# v1_1_0.net
KiCad netlist of a schematic drawn in EAGLE
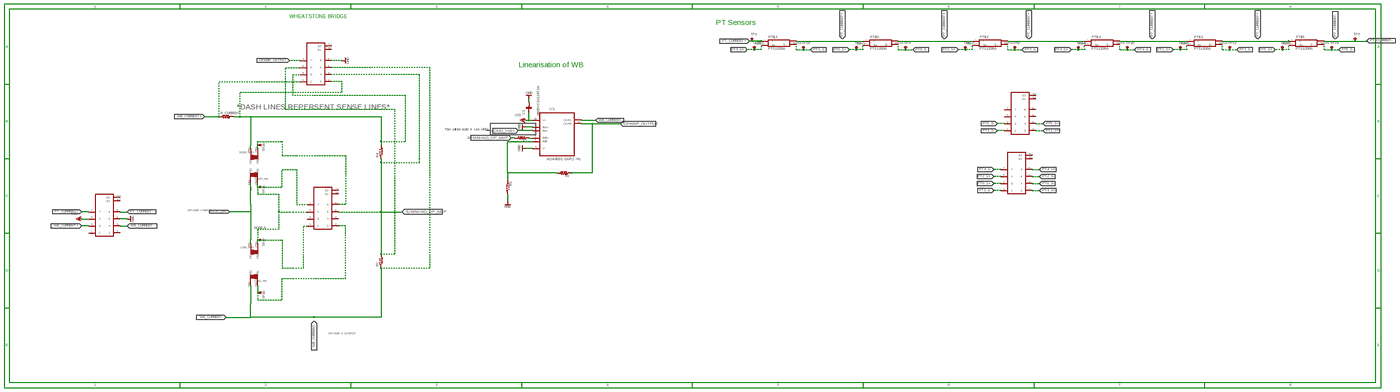
[diagram p0: schematic, sheet 1, overview]
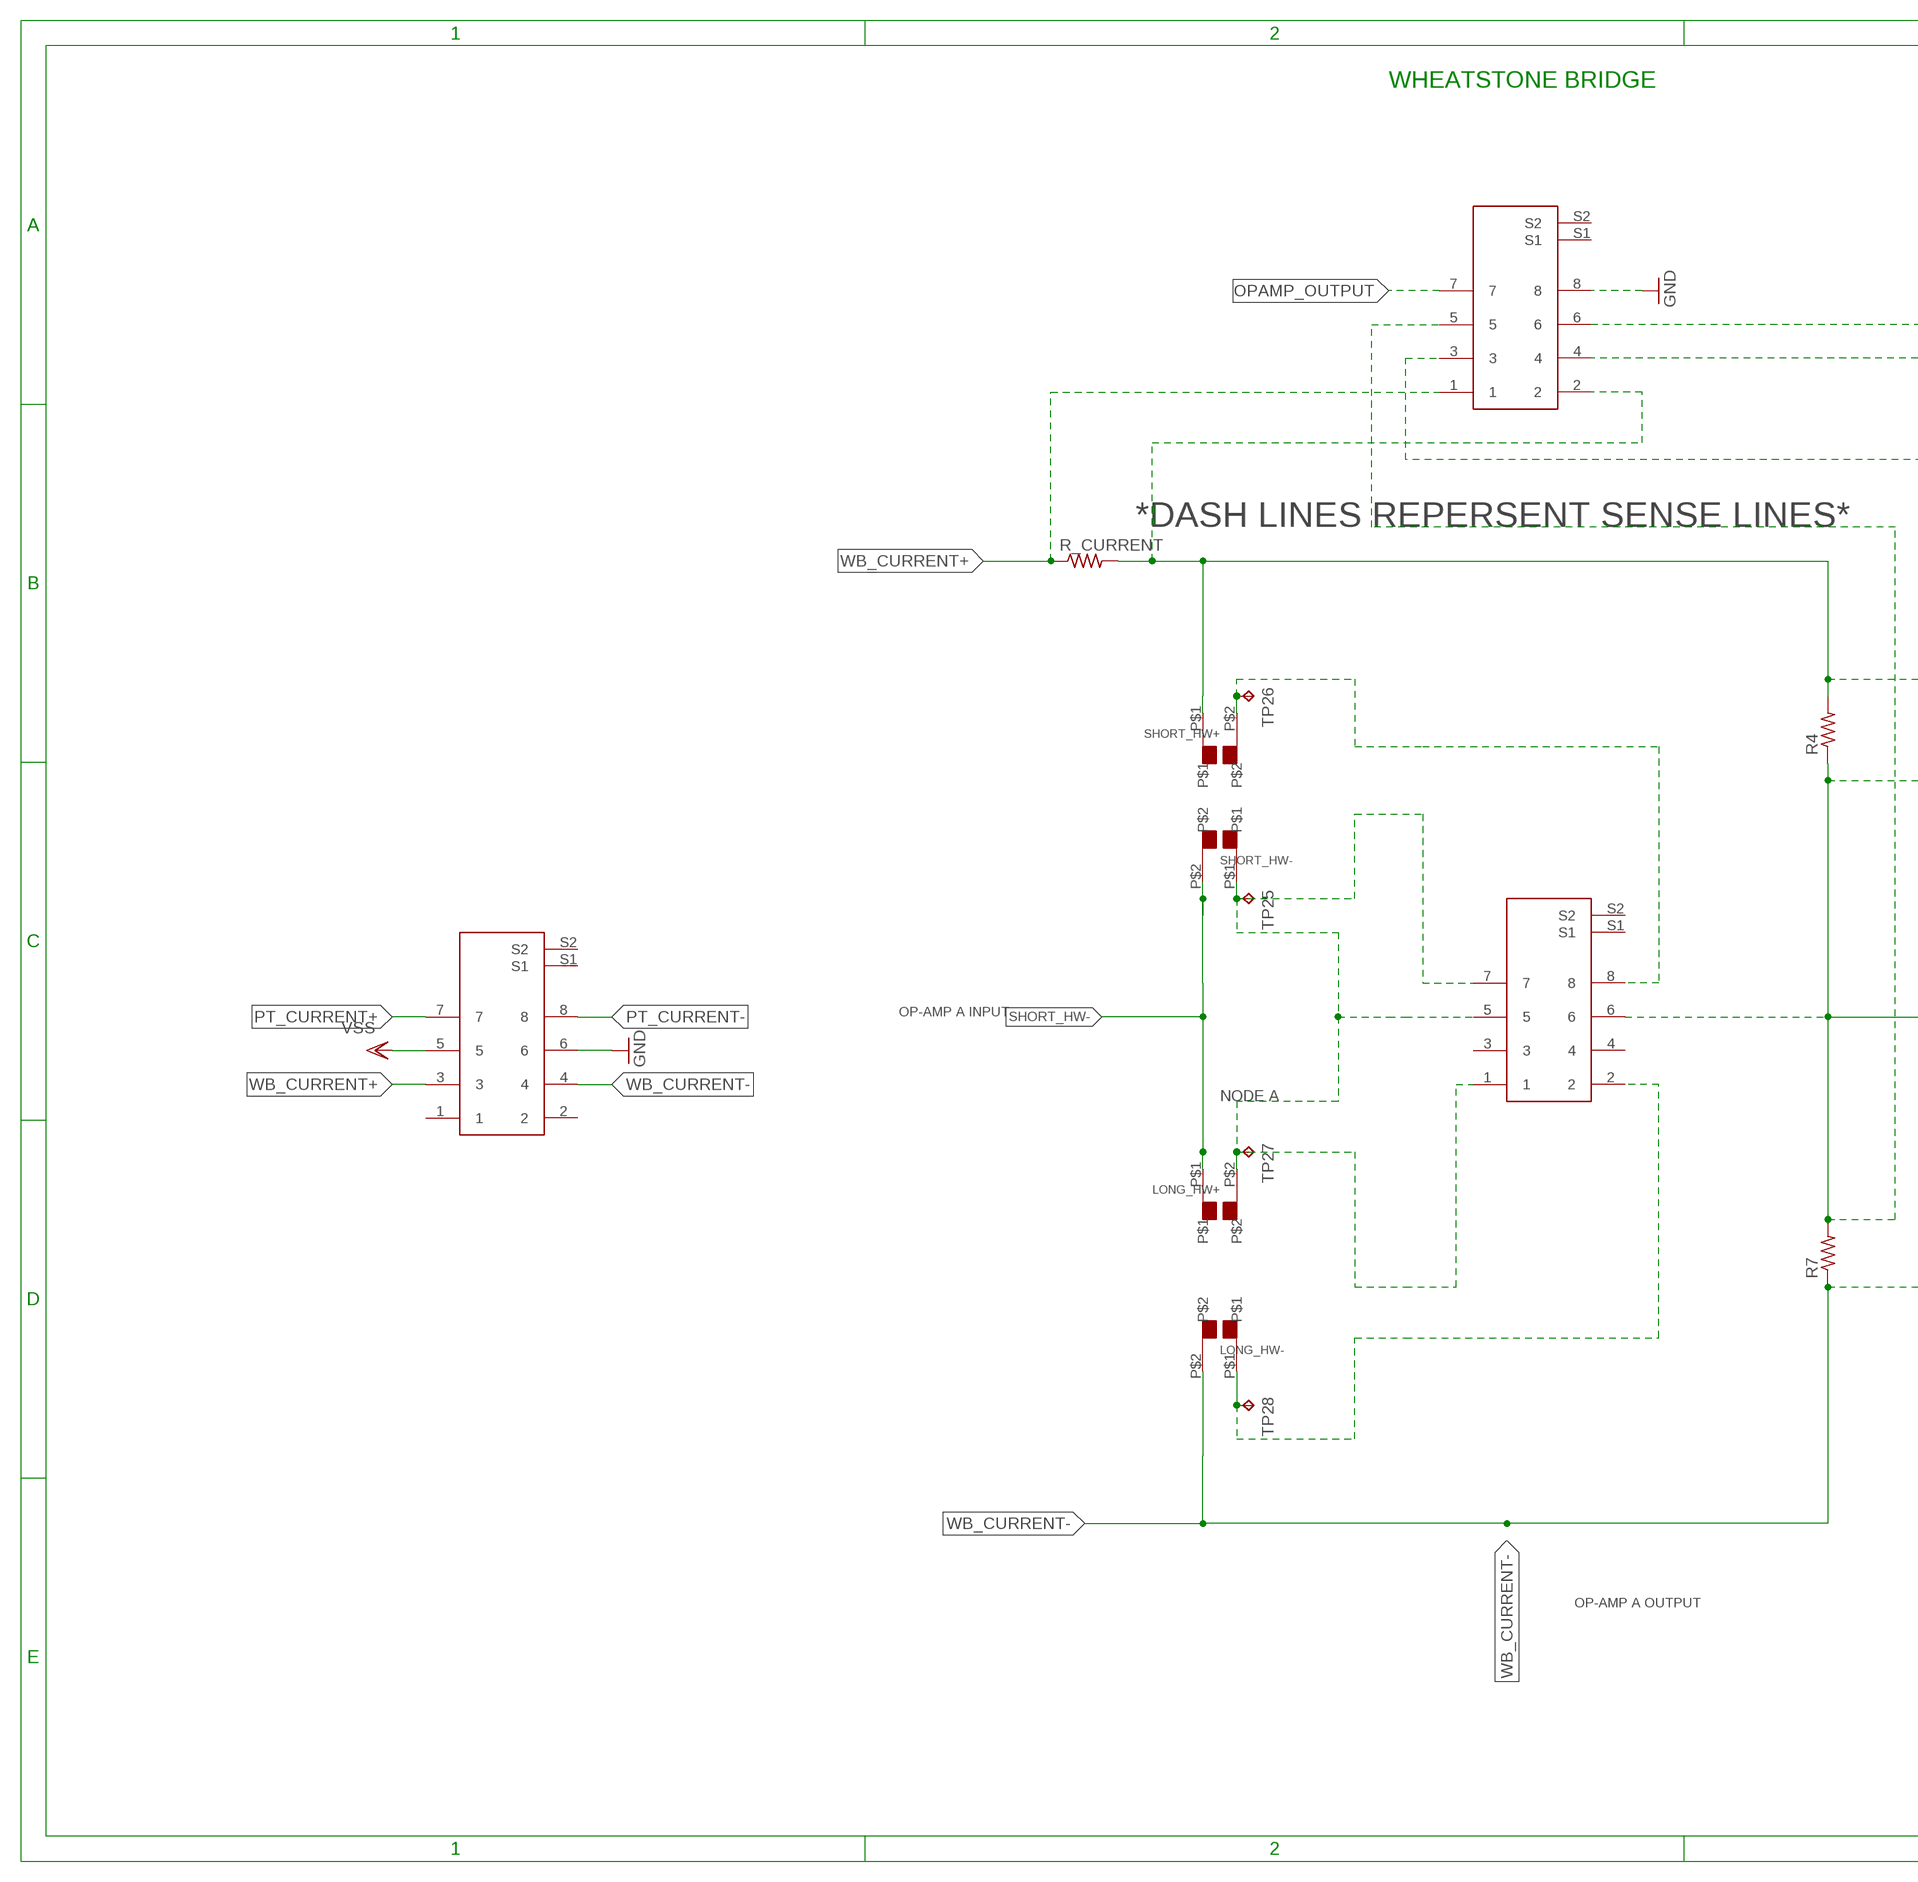
[diagram p1: schematic, sheet 1, part 1 of 4]
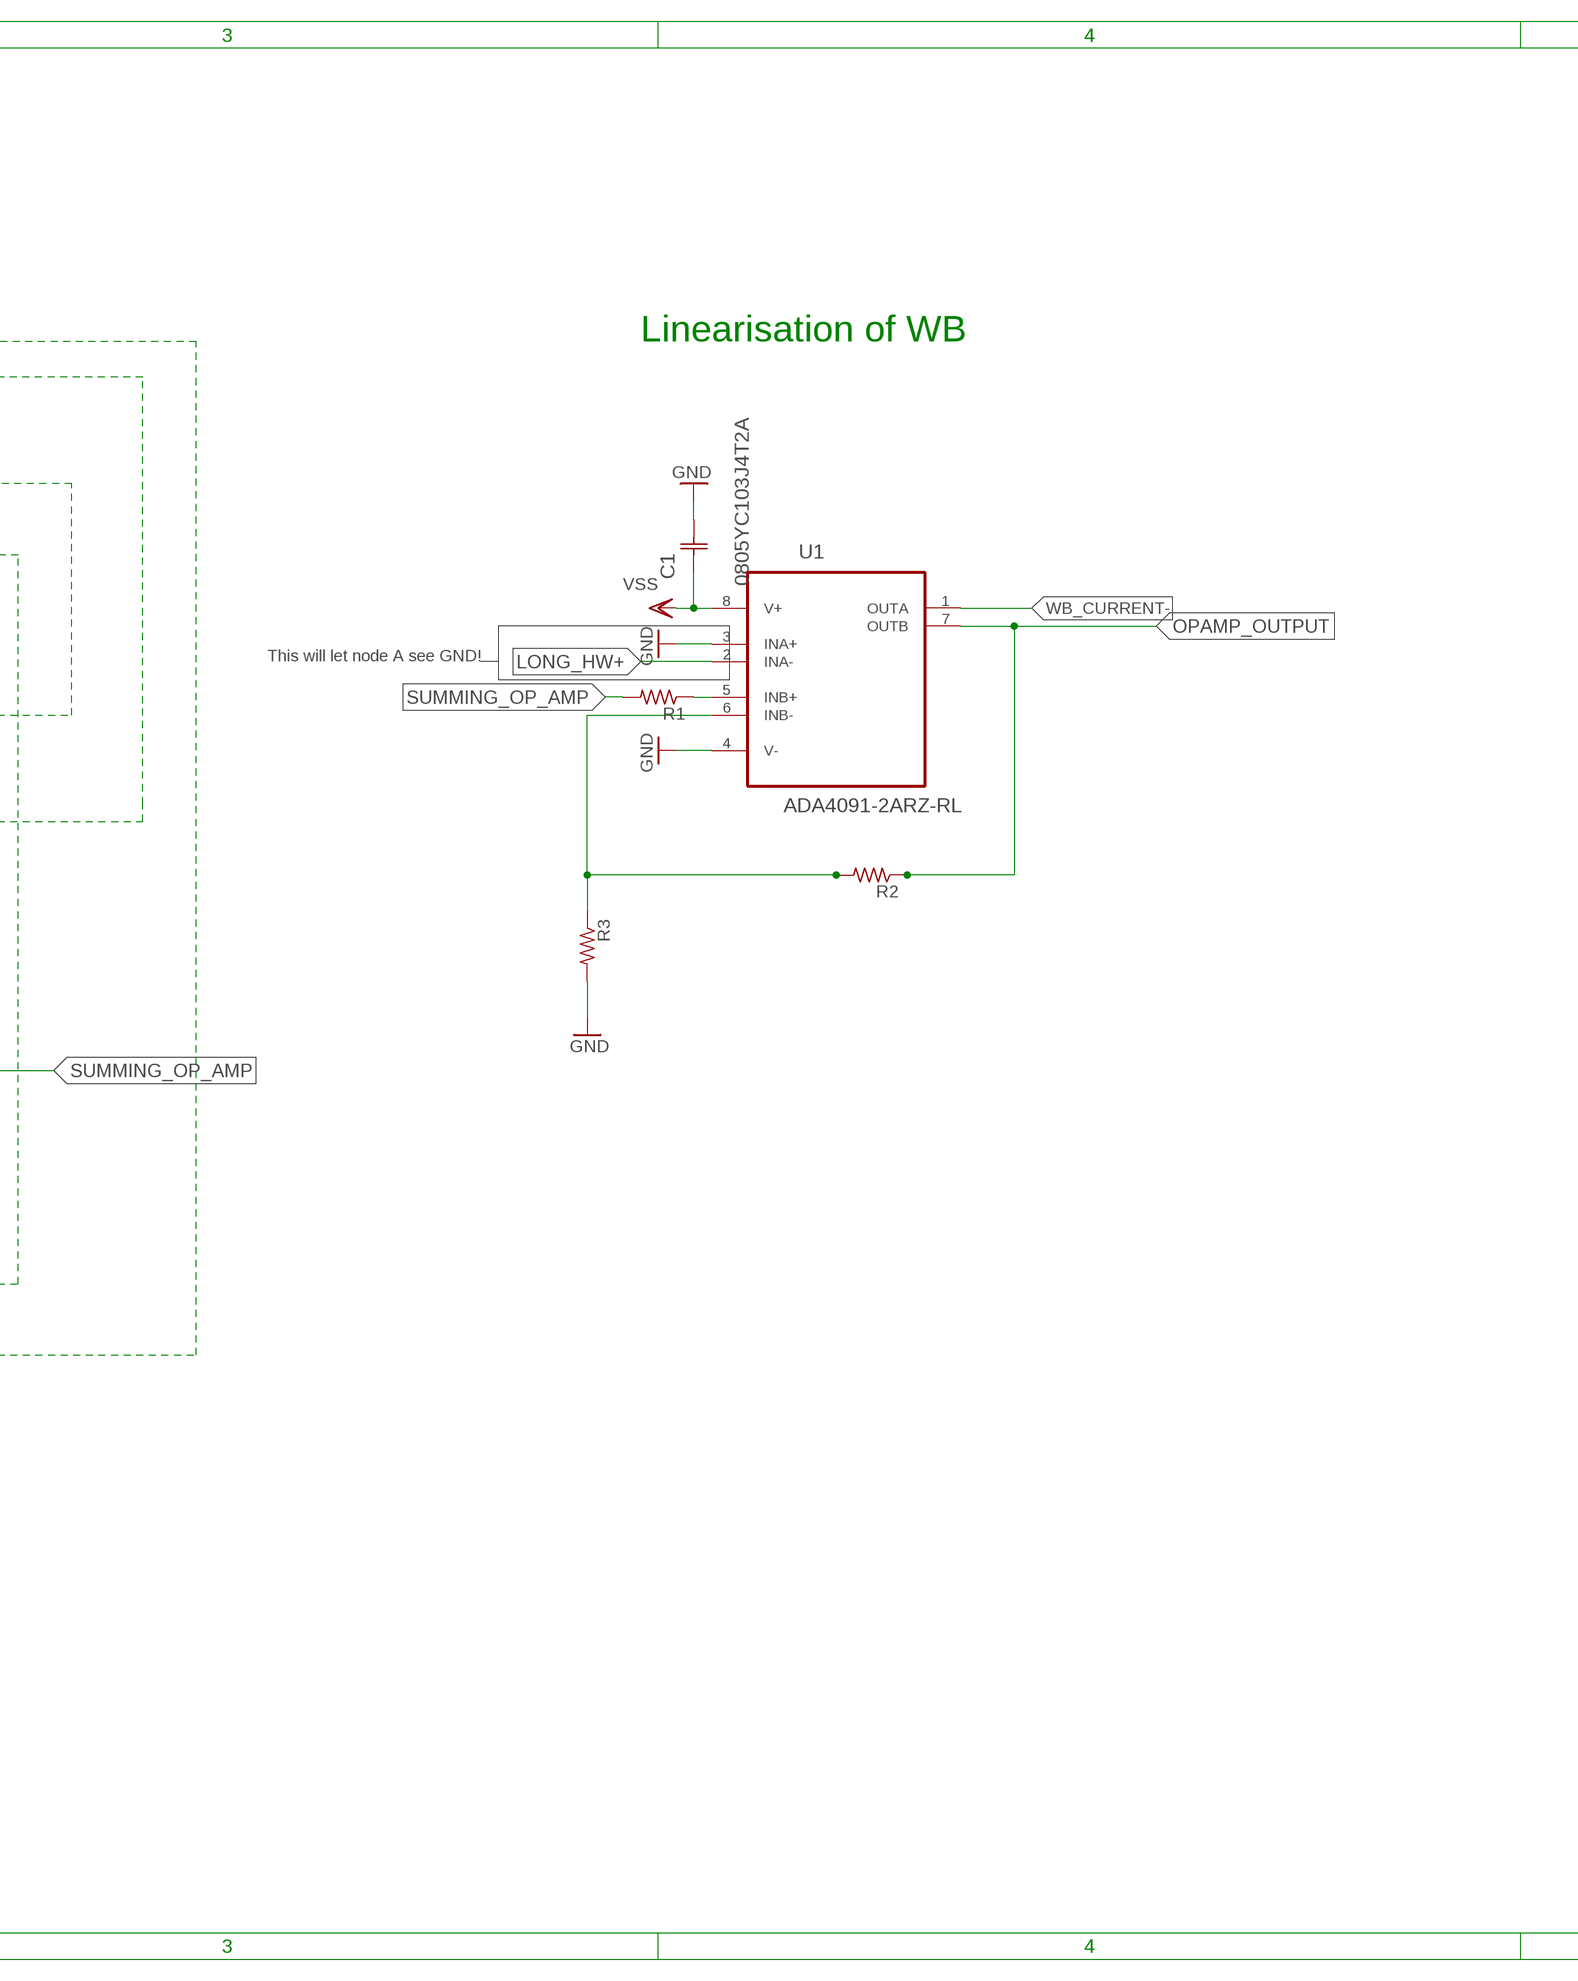
[diagram p2: schematic, sheet 1, part 2 of 4]
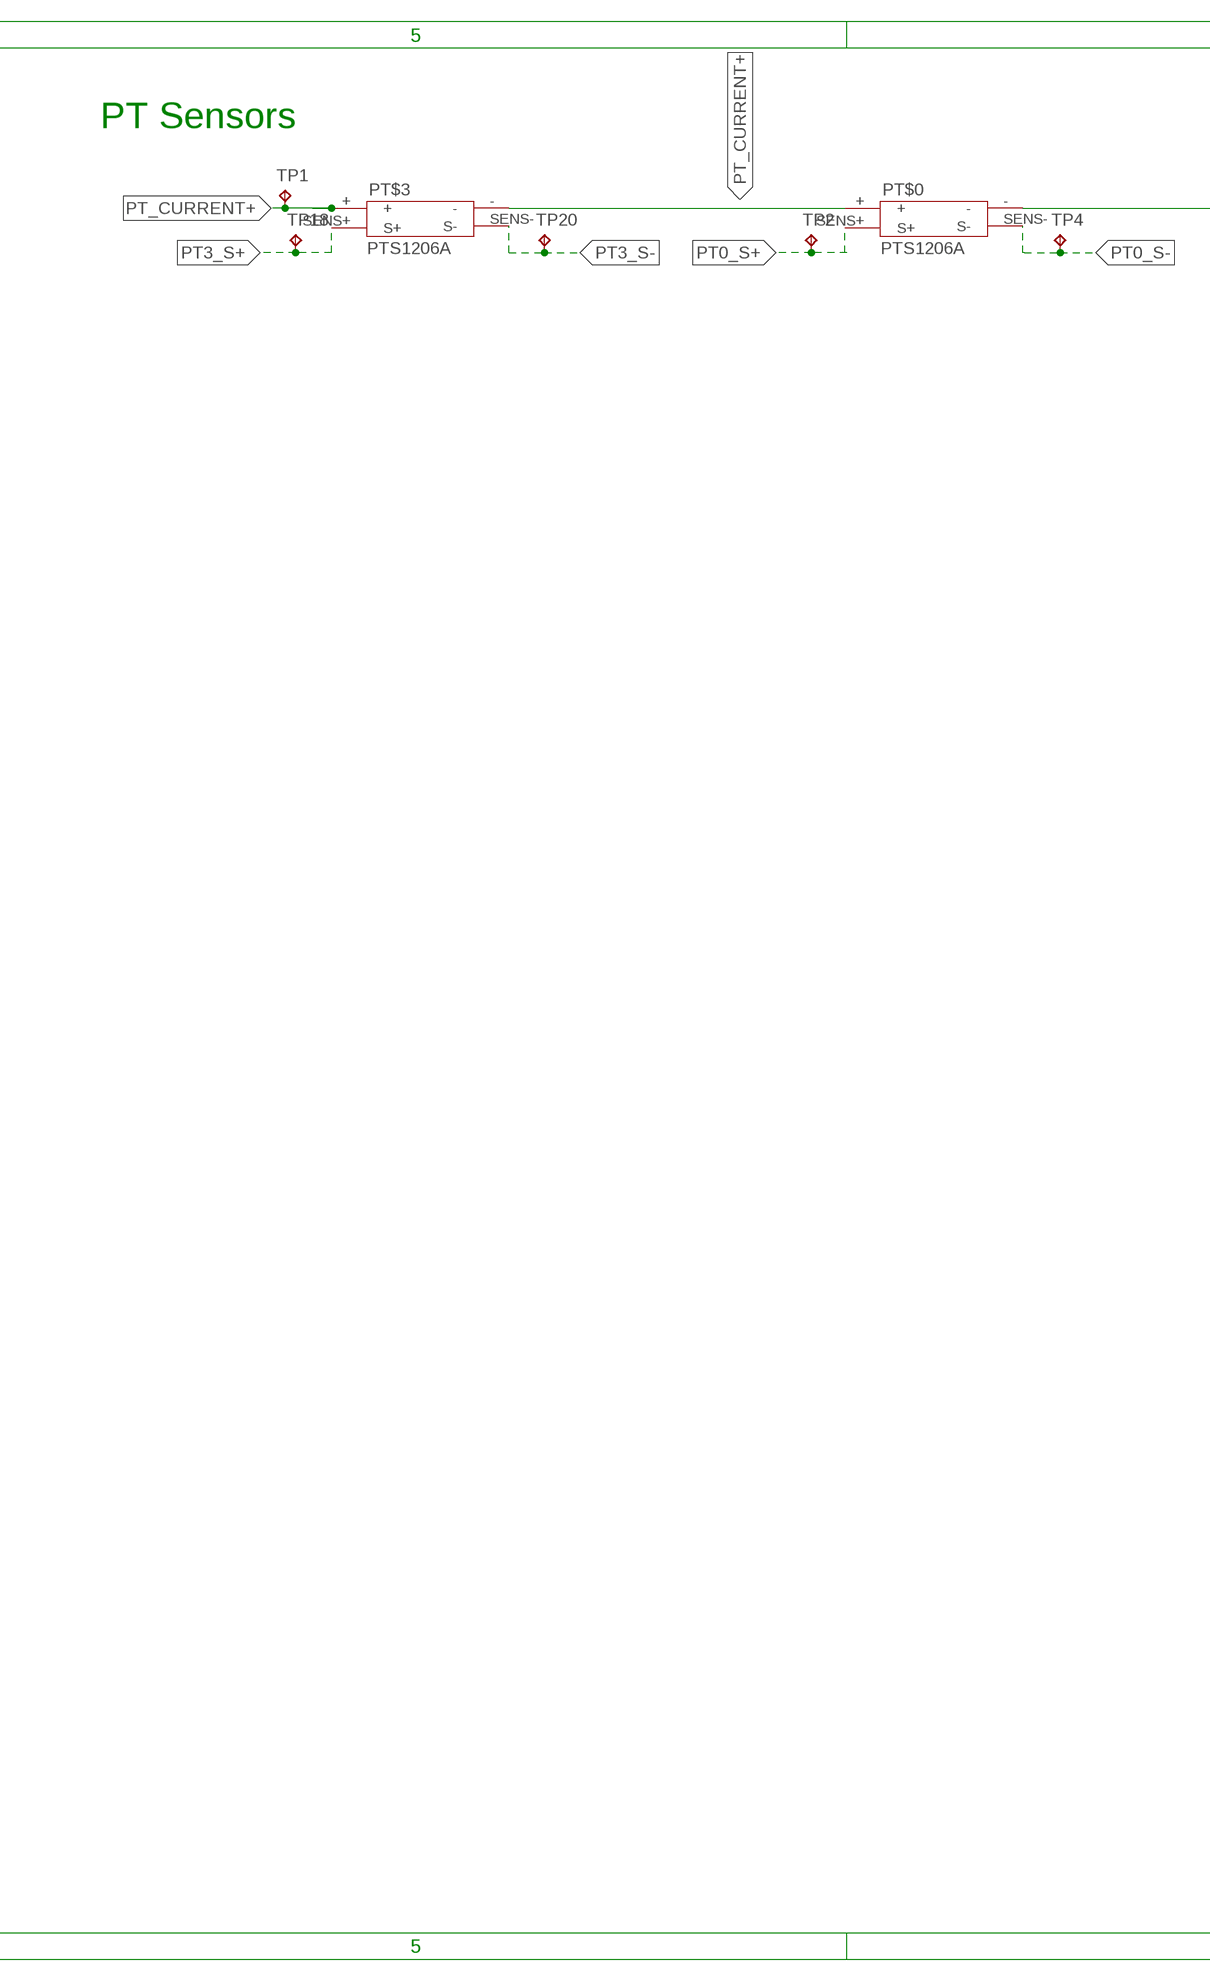
[diagram p3: schematic, sheet 1, part 3 of 4]
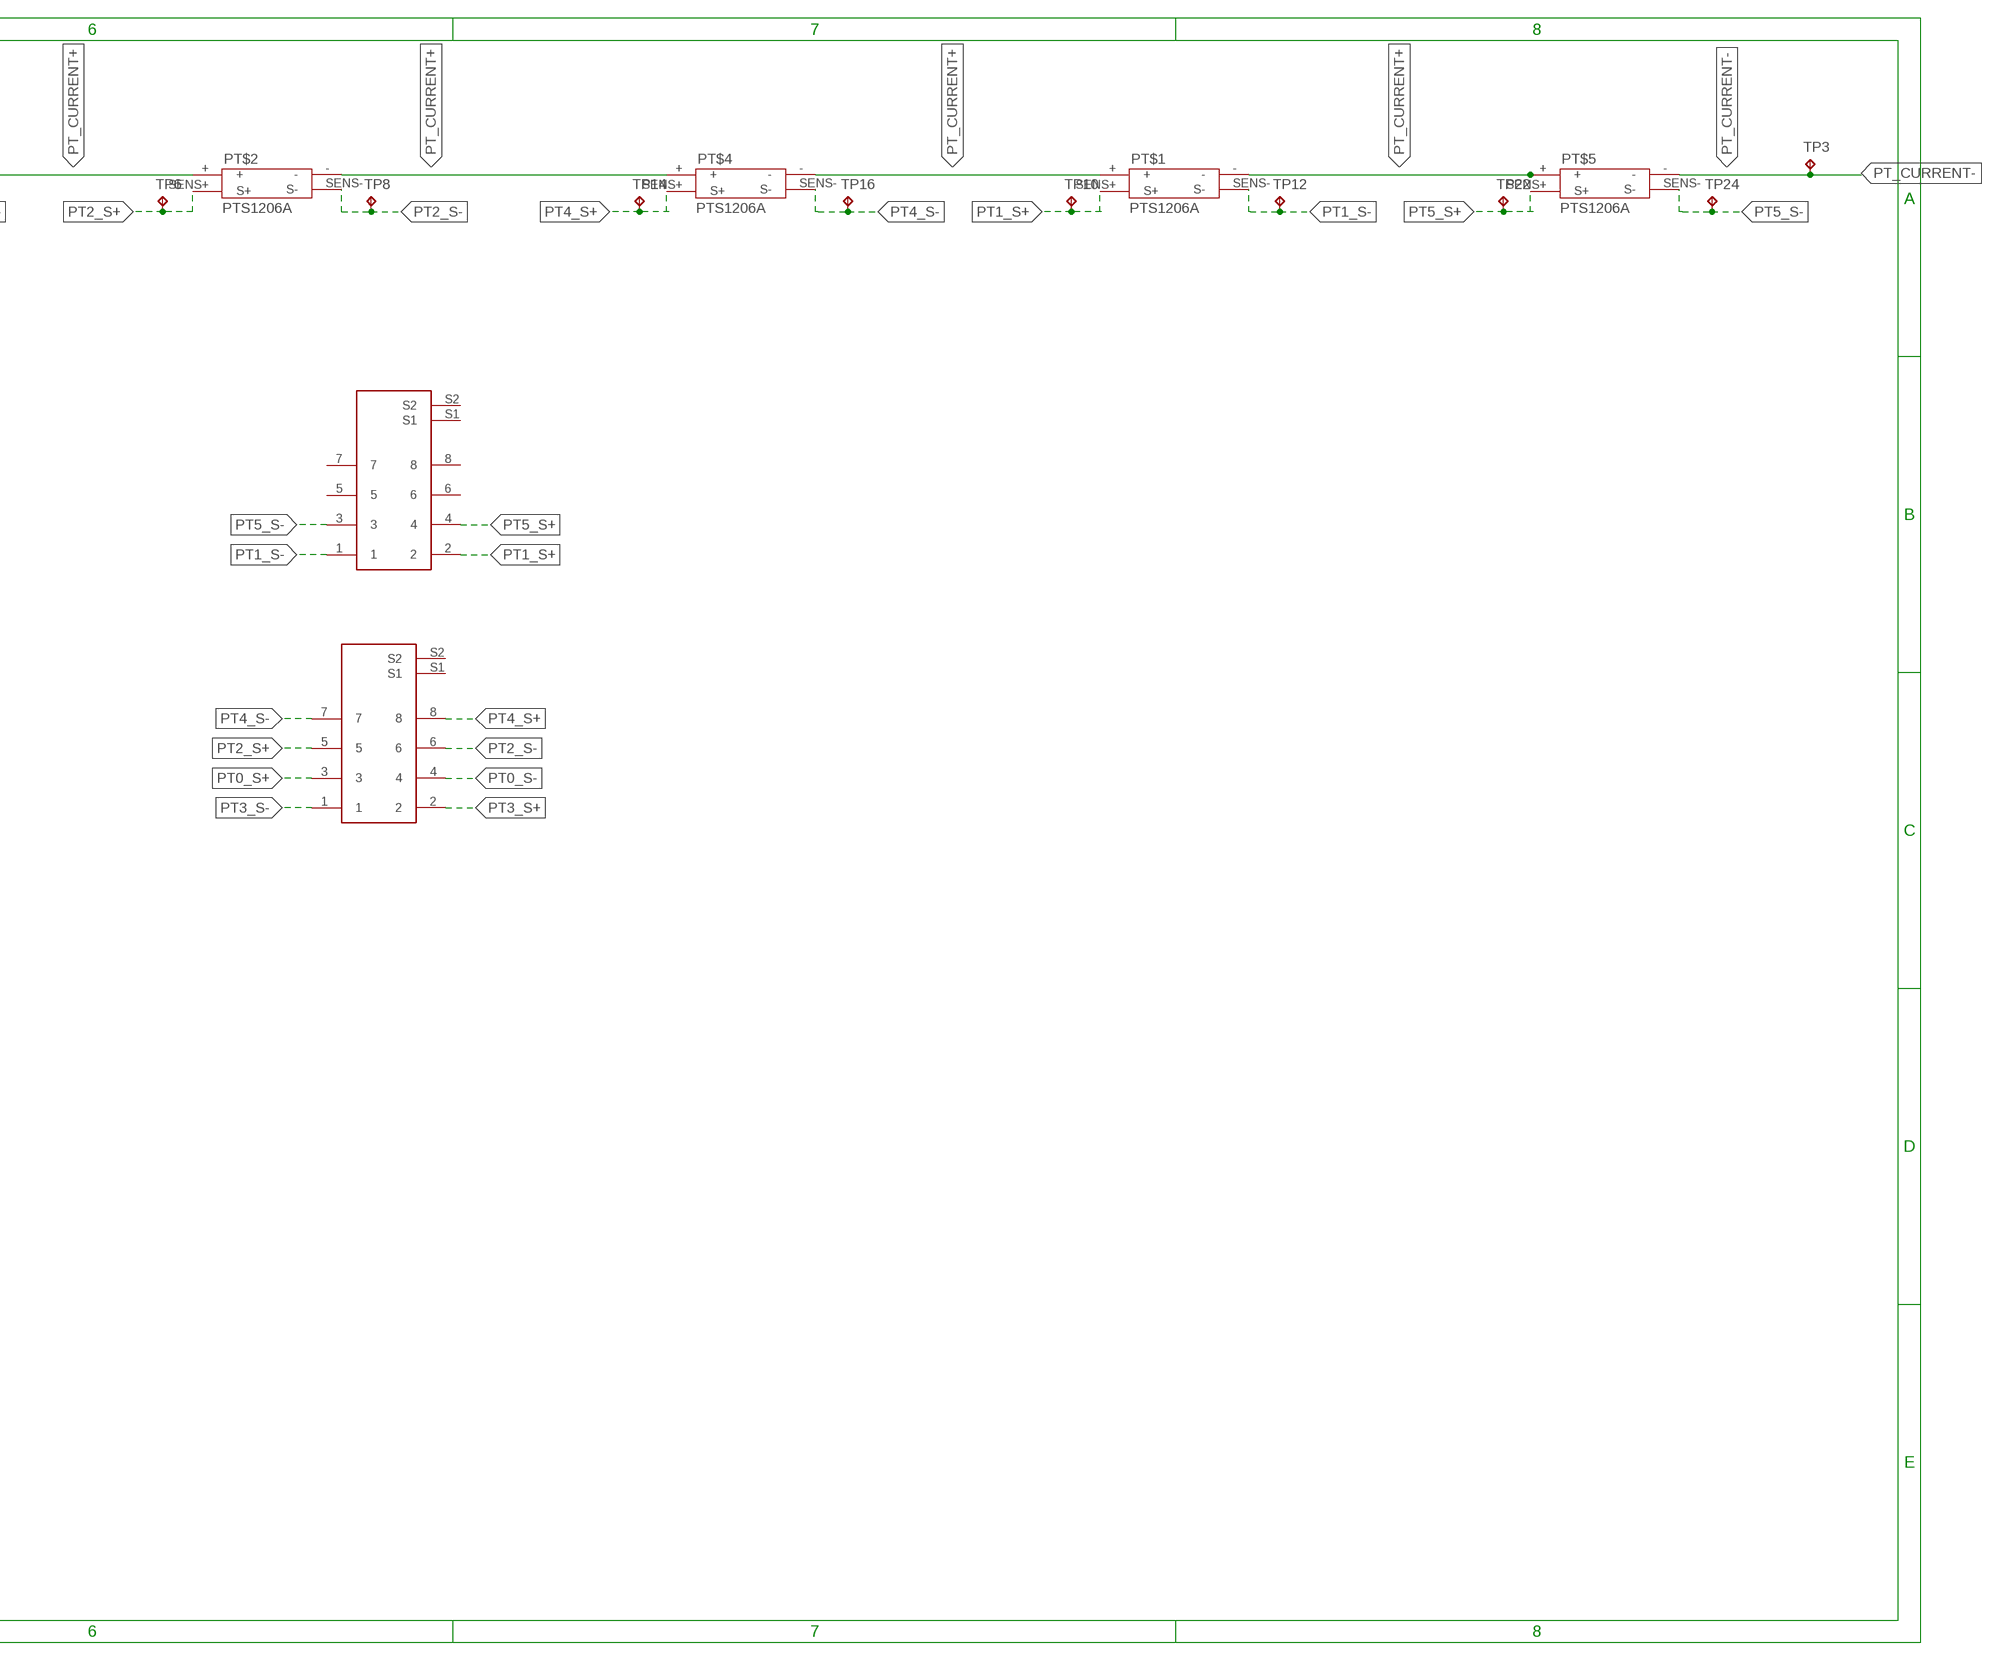
[diagram p4: schematic, sheet 1, part 4 of 4]

(export (version "E")
  (design (tool "Eeschema 10.0.6"))
  (components
    (comp (ref "C1")
      (value "0805YC103J4T2A")
      (footprint "eagle-import:CAPC2012X94N")
      (fields (field (name "MF") "AVX"))
      (libsource (lib "eagle-import") (part "0805YC103J4T2A"))
    )
    (comp (ref "LONG_HW+")
      (value "WIREPOINT_1A")
      (footprint "eagle-import:WIREPOINT")
      (libsource (lib "eagle-import") (part "WIREPOINT_1A"))
    )
    (comp (ref "LONG_HW-")
      (value "WIREPOINT_1A")
      (footprint "eagle-import:WIREPOINT")
      (libsource (lib "eagle-import") (part "WIREPOINT_1A"))
    )
    (comp (ref "POWER")
      (value "RJ45_CONNECTOR")
      (footprint "eagle-import:RJ45_CONNNECTOR")
      (libsource (lib "eagle-import") (part "RJ45_CONNECTOR"))
    )
    (comp (ref "PT$0")
      (value "PTS1206A")
      (footprint "eagle-import:CAPMP3216X166")
      (libsource (lib "eagle-import") (part "PTS1206A"))
    )
    (comp (ref "PT$1")
      (value "PTS1206A")
      (footprint "eagle-import:CAPMP3216X166")
      (libsource (lib "eagle-import") (part "PTS1206A"))
    )
    (comp (ref "PT$2")
      (value "PTS1206A")
      (footprint "eagle-import:CAPMP3216X166")
      (libsource (lib "eagle-import") (part "PTS1206A"))
    )
    (comp (ref "PT$3")
      (value "PTS1206A")
      (footprint "eagle-import:CAPMP3216X166")
      (libsource (lib "eagle-import") (part "PTS1206A"))
    )
    (comp (ref "PT$4")
      (value "PTS1206A")
      (footprint "eagle-import:CAPMP3216X166")
      (libsource (lib "eagle-import") (part "PTS1206A"))
    )
    (comp (ref "PT$5")
      (value "PTS1206A")
      (footprint "eagle-import:CAPMP3216X166")
      (libsource (lib "eagle-import") (part "PTS1206A"))
    )
    (comp (ref "PT_SENS1")
      (value "RJ45_CONNECTOR")
      (footprint "eagle-import:RJ45_CONNNECTOR")
      (libsource (lib "eagle-import") (part "RJ45_CONNECTOR"))
    )
    (comp (ref "PT_SENS2")
      (value "RJ45_CONNECTOR")
      (footprint "eagle-import:RJ45_CONNNECTOR")
      (libsource (lib "eagle-import") (part "RJ45_CONNECTOR"))
    )
    (comp (ref "R1")
      (value "R-US_M0805")
      (footprint "eagle-import:M0805")
      (libsource (lib "eagle-import") (part "R-US_M0805"))
    )
    (comp (ref "R2")
      (value "R-US_M0805")
      (footprint "eagle-import:M0805")
      (libsource (lib "eagle-import") (part "R-US_M0805"))
    )
    (comp (ref "R3")
      (value "R-US_M0805")
      (footprint "eagle-import:M0805")
      (libsource (lib "eagle-import") (part "R-US_M0805"))
    )
    (comp (ref "R4")
      (value "R-US_M0805")
      (footprint "eagle-import:M0805")
      (libsource (lib "eagle-import") (part "R-US_M0805"))
    )
    (comp (ref "R7")
      (value "R-US_M0805")
      (footprint "eagle-import:M0805")
      (libsource (lib "eagle-import") (part "R-US_M0805"))
    )
    (comp (ref "R_CURRENT")
      (value "R-US_M0805")
      (footprint "eagle-import:M0805")
      (libsource (lib "eagle-import") (part "R-US_M0805"))
    )
    (comp (ref "SHORT_HW+")
      (value "WIREPOINT_1A")
      (footprint "eagle-import:WIREPOINT")
      (libsource (lib "eagle-import") (part "WIREPOINT_1A"))
    )
    (comp (ref "SHORT_HW-")
      (value "WIREPOINT_1A")
      (footprint "eagle-import:WIREPOINT")
      (libsource (lib "eagle-import") (part "WIREPOINT_1A"))
    )
    (comp (ref "TP1")
      (value "TPTP10SQ")
      (footprint "eagle-import:TP10SQ")
      (libsource (lib "eagle-import") (part "TPTP10SQ"))
    )
    (comp (ref "TP2")
      (value "TPTP10SQ")
      (footprint "eagle-import:TP10SQ")
      (libsource (lib "eagle-import") (part "TPTP10SQ"))
    )
    (comp (ref "TP3")
      (value "TPTP10SQ")
      (footprint "eagle-import:TP10SQ")
      (libsource (lib "eagle-import") (part "TPTP10SQ"))
    )
    (comp (ref "TP4")
      (value "TPTP10SQ")
      (footprint "eagle-import:TP10SQ")
      (libsource (lib "eagle-import") (part "TPTP10SQ"))
    )
    (comp (ref "TP6")
      (value "TPTP10SQ")
      (footprint "eagle-import:TP10SQ")
      (libsource (lib "eagle-import") (part "TPTP10SQ"))
    )
    (comp (ref "TP8")
      (value "TPTP10SQ")
      (footprint "eagle-import:TP10SQ")
      (libsource (lib "eagle-import") (part "TPTP10SQ"))
    )
    (comp (ref "TP10")
      (value "TPTP10SQ")
      (footprint "eagle-import:TP10SQ")
      (libsource (lib "eagle-import") (part "TPTP10SQ"))
    )
    (comp (ref "TP12")
      (value "TPTP10SQ")
      (footprint "eagle-import:TP10SQ")
      (libsource (lib "eagle-import") (part "TPTP10SQ"))
    )
    (comp (ref "TP14")
      (value "TPTP10SQ")
      (footprint "eagle-import:TP10SQ")
      (libsource (lib "eagle-import") (part "TPTP10SQ"))
    )
    (comp (ref "TP16")
      (value "TPTP10SQ")
      (footprint "eagle-import:TP10SQ")
      (libsource (lib "eagle-import") (part "TPTP10SQ"))
    )
    (comp (ref "TP18")
      (value "TPTP10SQ")
      (footprint "eagle-import:TP10SQ")
      (libsource (lib "eagle-import") (part "TPTP10SQ"))
    )
    (comp (ref "TP20")
      (value "TPTP10SQ")
      (footprint "eagle-import:TP10SQ")
      (libsource (lib "eagle-import") (part "TPTP10SQ"))
    )
    (comp (ref "TP22")
      (value "TPTP10SQ")
      (footprint "eagle-import:TP10SQ")
      (libsource (lib "eagle-import") (part "TPTP10SQ"))
    )
    (comp (ref "TP24")
      (value "TPTP10SQ")
      (footprint "eagle-import:TP10SQ")
      (libsource (lib "eagle-import") (part "TPTP10SQ"))
    )
    (comp (ref "TP25")
      (value "TPTP10SQ")
      (footprint "eagle-import:TP10SQ")
      (libsource (lib "eagle-import") (part "TPTP10SQ"))
    )
    (comp (ref "TP26")
      (value "TPTP10SQ")
      (footprint "eagle-import:TP10SQ")
      (libsource (lib "eagle-import") (part "TPTP10SQ"))
    )
    (comp (ref "TP27")
      (value "TPTP10SQ")
      (footprint "eagle-import:TP10SQ")
      (libsource (lib "eagle-import") (part "TPTP10SQ"))
    )
    (comp (ref "TP28")
      (value "TPTP10SQ")
      (footprint "eagle-import:TP10SQ")
      (libsource (lib "eagle-import") (part "TPTP10SQ"))
    )
    (comp (ref "U1")
      (value "ADA4091-2ARZ-RL")
      (footprint "eagle-import:SOIC127P600X175-8N")
      (fields (field (name "MF") "Analog"))
      (libsource (lib "eagle-import") (part "ADA4091-2ARZ-RL"))
    )
    (comp (ref "WB_SENS1")
      (value "RJ45_CONNECTOR")
      (footprint "eagle-import:RJ45_CONNNECTOR")
      (libsource (lib "eagle-import") (part "RJ45_CONNECTOR"))
    )
    (comp (ref "WB_SENS2")
      (value "RJ45_CONNECTOR")
      (footprint "eagle-import:RJ45_CONNNECTOR")
      (libsource (lib "eagle-import") (part "RJ45_CONNECTOR"))
    )
  )
  (nets
    (net (code "1") (name "GND") (class "Default")
      (node (ref "C1") (pin "2") (pinfunction "C2_2") (pintype "passive"))
      (node (ref "POWER") (pin "6") (pinfunction "6_6") (pintype "bidirectional"))
      (node (ref "R3") (pin "2") (pinfunction "2_2") (pintype "passive"))
      (node (ref "U1") (pin "3") (pinfunction "INA+_3") (pintype "input"))
      (node (ref "U1") (pin "4") (pinfunction "V-_4") (pintype "power_in"))
      (node (ref "WB_SENS2") (pin "8") (pinfunction "8_8") (pintype "bidirectional"))
    )
    (net (code "2") (name "LONG_HW+") (class "Default")
      (node (ref "U1") (pin "2") (pinfunction "INA-_2") (pintype "input"))
    )
    (net (code "3") (name "Net-(LONG_HW+-PadP$2)") (class "Default")
      (node (ref "LONG_HW+") (pin "P$2") (pinfunction "P$2_P$2") (pintype "bidirectional"))
      (node (ref "SHORT_HW-") (pin "P$1") (pinfunction "P$1_P$1") (pintype "bidirectional"))
      (node (ref "TP25") (pin "TP") (pinfunction "TP_TP") (pintype "input"))
      (node (ref "TP27") (pin "TP") (pinfunction "TP_TP") (pintype "input"))
      (node (ref "WB_SENS1") (pin "1") (pinfunction "1_1") (pintype "bidirectional"))
      (node (ref "WB_SENS1") (pin "5") (pinfunction "5_5") (pintype "bidirectional"))
      (node (ref "WB_SENS1") (pin "7") (pinfunction "7_7") (pintype "bidirectional"))
    )
    (net (code "4") (name "Net-(LONG_HW--PadP$1)") (class "Default")
      (node (ref "LONG_HW-") (pin "P$1") (pinfunction "P$1_P$1") (pintype "bidirectional"))
      (node (ref "TP28") (pin "TP") (pinfunction "TP_TP") (pintype "input"))
      (node (ref "WB_SENS1") (pin "2") (pinfunction "2_2") (pintype "bidirectional"))
    )
    (net (code "5") (name "Net-(SHORT_HW+-PadP$2)") (class "Default")
      (node (ref "SHORT_HW+") (pin "P$2") (pinfunction "P$2_P$2") (pintype "bidirectional"))
      (node (ref "TP26") (pin "TP") (pinfunction "TP_TP") (pintype "input"))
      (node (ref "WB_SENS1") (pin "8") (pinfunction "8_8") (pintype "bidirectional"))
    )
    (net (code "6") (name "Net-(U1-INB+)") (class "Default")
      (node (ref "R1") (pin "1") (pinfunction "1_1") (pintype "passive"))
      (node (ref "U1") (pin "5") (pinfunction "INB+_5") (pintype "input"))
    )
    (net (code "7") (name "Net-(U1-INB-)") (class "Default")
      (node (ref "R2") (pin "2") (pinfunction "2_2") (pintype "passive"))
      (node (ref "R3") (pin "1") (pinfunction "1_1") (pintype "passive"))
      (node (ref "U1") (pin "6") (pinfunction "INB-_6") (pintype "input"))
    )
    (net (code "8") (name "OPAMP_OUTPUT") (class "Default")
      (node (ref "R2") (pin "1") (pinfunction "1_1") (pintype "passive"))
      (node (ref "U1") (pin "7") (pinfunction "OUTB_7") (pintype "output"))
      (node (ref "WB_SENS2") (pin "7") (pinfunction "7_7") (pintype "bidirectional"))
    )
    (net (code "9") (name "PT0_S+") (class "Default")
      (node (ref "PT$0") (pin "SENS+") (pinfunction "S+_SENS+") (pintype "bidirectional"))
      (node (ref "PT_SENS2") (pin "3") (pinfunction "3_3") (pintype "bidirectional"))
      (node (ref "TP2") (pin "TP") (pinfunction "TP_TP") (pintype "input"))
    )
    (net (code "10") (name "PT0_S-") (class "Default")
      (node (ref "PT$0") (pin "SENS-") (pinfunction "S-_SENS-") (pintype "bidirectional"))
      (node (ref "PT_SENS2") (pin "4") (pinfunction "4_4") (pintype "bidirectional"))
      (node (ref "TP4") (pin "TP") (pinfunction "TP_TP") (pintype "input"))
    )
    (net (code "11") (name "PT1_S+") (class "Default")
      (node (ref "PT$1") (pin "SENS+") (pinfunction "S+_SENS+") (pintype "bidirectional"))
      (node (ref "PT_SENS1") (pin "2") (pinfunction "2_2") (pintype "bidirectional"))
      (node (ref "TP10") (pin "TP") (pinfunction "TP_TP") (pintype "input"))
    )
    (net (code "12") (name "PT1_S-") (class "Default")
      (node (ref "PT$1") (pin "SENS-") (pinfunction "S-_SENS-") (pintype "bidirectional"))
      (node (ref "PT_SENS1") (pin "1") (pinfunction "1_1") (pintype "bidirectional"))
      (node (ref "TP12") (pin "TP") (pinfunction "TP_TP") (pintype "input"))
    )
    (net (code "13") (name "PT2_S+") (class "Default")
      (node (ref "PT$2") (pin "SENS+") (pinfunction "S+_SENS+") (pintype "bidirectional"))
      (node (ref "PT_SENS2") (pin "5") (pinfunction "5_5") (pintype "bidirectional"))
      (node (ref "TP6") (pin "TP") (pinfunction "TP_TP") (pintype "input"))
    )
    (net (code "14") (name "PT2_S-") (class "Default")
      (node (ref "PT$2") (pin "SENS-") (pinfunction "S-_SENS-") (pintype "bidirectional"))
      (node (ref "PT_SENS2") (pin "6") (pinfunction "6_6") (pintype "bidirectional"))
      (node (ref "TP8") (pin "TP") (pinfunction "TP_TP") (pintype "input"))
    )
    (net (code "15") (name "PT3_S+") (class "Default")
      (node (ref "PT$3") (pin "SENS+") (pinfunction "S+_SENS+") (pintype "bidirectional"))
      (node (ref "PT_SENS2") (pin "2") (pinfunction "2_2") (pintype "bidirectional"))
      (node (ref "TP18") (pin "TP") (pinfunction "TP_TP") (pintype "input"))
    )
    (net (code "16") (name "PT3_S-") (class "Default")
      (node (ref "PT$3") (pin "SENS-") (pinfunction "S-_SENS-") (pintype "bidirectional"))
      (node (ref "PT_SENS2") (pin "1") (pinfunction "1_1") (pintype "bidirectional"))
      (node (ref "TP20") (pin "TP") (pinfunction "TP_TP") (pintype "input"))
    )
    (net (code "17") (name "PT4_S+") (class "Default")
      (node (ref "PT$4") (pin "SENS+") (pinfunction "S+_SENS+") (pintype "bidirectional"))
      (node (ref "PT_SENS2") (pin "8") (pinfunction "8_8") (pintype "bidirectional"))
      (node (ref "TP14") (pin "TP") (pinfunction "TP_TP") (pintype "input"))
    )
    (net (code "18") (name "PT4_S-") (class "Default")
      (node (ref "PT$4") (pin "SENS-") (pinfunction "S-_SENS-") (pintype "bidirectional"))
      (node (ref "PT_SENS2") (pin "7") (pinfunction "7_7") (pintype "bidirectional"))
      (node (ref "TP16") (pin "TP") (pinfunction "TP_TP") (pintype "input"))
    )
    (net (code "19") (name "PT5_S+") (class "Default")
      (node (ref "PT$5") (pin "SENS+") (pinfunction "S+_SENS+") (pintype "bidirectional"))
      (node (ref "PT_SENS1") (pin "4") (pinfunction "4_4") (pintype "bidirectional"))
      (node (ref "TP22") (pin "TP") (pinfunction "TP_TP") (pintype "input"))
    )
    (net (code "20") (name "PT5_S-") (class "Default")
      (node (ref "PT$5") (pin "SENS-") (pinfunction "S-_SENS-") (pintype "bidirectional"))
      (node (ref "PT_SENS1") (pin "3") (pinfunction "3_3") (pintype "bidirectional"))
      (node (ref "TP24") (pin "TP") (pinfunction "TP_TP") (pintype "input"))
    )
    (net (code "21") (name "PT_CURRENT+") (class "Default")
      (node (ref "POWER") (pin "7") (pinfunction "7_7") (pintype "bidirectional"))
      (node (ref "PT$0") (pin "+") (pinfunction "+_+") (pintype "bidirectional"))
      (node (ref "PT$0") (pin "-") (pinfunction "-_-") (pintype "bidirectional"))
      (node (ref "PT$1") (pin "+") (pinfunction "+_+") (pintype "bidirectional"))
      (node (ref "PT$1") (pin "-") (pinfunction "-_-") (pintype "bidirectional"))
      (node (ref "PT$2") (pin "+") (pinfunction "+_+") (pintype "bidirectional"))
      (node (ref "PT$2") (pin "-") (pinfunction "-_-") (pintype "bidirectional"))
      (node (ref "PT$3") (pin "+") (pinfunction "+_+") (pintype "bidirectional"))
      (node (ref "PT$3") (pin "-") (pinfunction "-_-") (pintype "bidirectional"))
      (node (ref "PT$4") (pin "+") (pinfunction "+_+") (pintype "bidirectional"))
      (node (ref "PT$4") (pin "-") (pinfunction "-_-") (pintype "bidirectional"))
      (node (ref "PT$5") (pin "+") (pinfunction "+_+") (pintype "bidirectional"))
      (node (ref "TP1") (pin "TP") (pinfunction "TP_TP") (pintype "input"))
    )
    (net (code "22") (name "PT_CURRENT-") (class "Default")
      (node (ref "POWER") (pin "8") (pinfunction "8_8") (pintype "bidirectional"))
      (node (ref "PT$5") (pin "-") (pinfunction "-_-") (pintype "bidirectional"))
      (node (ref "TP3") (pin "TP") (pinfunction "TP_TP") (pintype "input"))
    )
    (net (code "23") (name "SHORT_HW+") (class "Default")
      (node (ref "R4") (pin "2") (pinfunction "2_2") (pintype "passive"))
      (node (ref "R_CURRENT") (pin "2") (pinfunction "2_2") (pintype "passive"))
      (node (ref "SHORT_HW+") (pin "P$1") (pinfunction "P$1_P$1") (pintype "bidirectional"))
      (node (ref "WB_SENS2") (pin "2") (pinfunction "2_2") (pintype "bidirectional"))
      (node (ref "WB_SENS2") (pin "3") (pinfunction "3_3") (pintype "bidirectional"))
    )
    (net (code "24") (name "SHORT_HW-") (class "Default")
      (node (ref "LONG_HW+") (pin "P$1") (pinfunction "P$1_P$1") (pintype "bidirectional"))
      (node (ref "SHORT_HW-") (pin "P$2") (pinfunction "P$2_P$2") (pintype "bidirectional"))
    )
    (net (code "25") (name "SUMMING_OP_AMP") (class "Default")
      (node (ref "R1") (pin "2") (pinfunction "2_2") (pintype "passive"))
      (node (ref "R4") (pin "1") (pinfunction "1_1") (pintype "passive"))
      (node (ref "R7") (pin "2") (pinfunction "2_2") (pintype "passive"))
      (node (ref "WB_SENS1") (pin "6") (pinfunction "6_6") (pintype "bidirectional"))
      (node (ref "WB_SENS2") (pin "4") (pinfunction "4_4") (pintype "bidirectional"))
      (node (ref "WB_SENS2") (pin "5") (pinfunction "5_5") (pintype "bidirectional"))
    )
    (net (code "26") (name "VSS") (class "Default")
      (node (ref "C1") (pin "1") (pinfunction "C1_1") (pintype "passive"))
      (node (ref "POWER") (pin "5") (pinfunction "5_5") (pintype "bidirectional"))
      (node (ref "U1") (pin "8") (pinfunction "V+_8") (pintype "power_in"))
    )
    (net (code "27") (name "WB_CURRENT+") (class "Default")
      (node (ref "POWER") (pin "3") (pinfunction "3_3") (pintype "bidirectional"))
      (node (ref "R_CURRENT") (pin "1") (pinfunction "1_1") (pintype "passive"))
      (node (ref "WB_SENS2") (pin "1") (pinfunction "1_1") (pintype "bidirectional"))
    )
    (net (code "28") (name "WB_CURRENT-") (class "Default")
      (node (ref "LONG_HW-") (pin "P$2") (pinfunction "P$2_P$2") (pintype "bidirectional"))
      (node (ref "POWER") (pin "4") (pinfunction "4_4") (pintype "bidirectional"))
      (node (ref "R7") (pin "1") (pinfunction "1_1") (pintype "passive"))
      (node (ref "U1") (pin "1") (pinfunction "OUTA_1") (pintype "output"))
      (node (ref "WB_SENS2") (pin "6") (pinfunction "6_6") (pintype "bidirectional"))
    )
    (net (code "29") (name "unconnected-(POWER-Pad1)") (class "Default")
      (node (ref "POWER") (pin "1") (pinfunction "1_1") (pintype "bidirectional"))
    )
    (net (code "30") (name "unconnected-(POWER-Pad2)") (class "Default")
      (node (ref "POWER") (pin "2") (pinfunction "2_2") (pintype "bidirectional"))
    )
    (net (code "31") (name "unconnected-(POWER-PadS1)") (class "Default")
      (node (ref "POWER") (pin "S1") (pinfunction "S1_S1") (pintype "bidirectional"))
    )
    (net (code "32") (name "unconnected-(POWER-PadS2)") (class "Default")
      (node (ref "POWER") (pin "S2") (pinfunction "S2_S2") (pintype "bidirectional"))
    )
    (net (code "33") (name "unconnected-(PT_SENS1-Pad5)") (class "Default")
      (node (ref "PT_SENS1") (pin "5") (pinfunction "5_5") (pintype "bidirectional"))
    )
    (net (code "34") (name "unconnected-(PT_SENS1-Pad6)") (class "Default")
      (node (ref "PT_SENS1") (pin "6") (pinfunction "6_6") (pintype "bidirectional"))
    )
    (net (code "35") (name "unconnected-(PT_SENS1-Pad7)") (class "Default")
      (node (ref "PT_SENS1") (pin "7") (pinfunction "7_7") (pintype "bidirectional"))
    )
    (net (code "36") (name "unconnected-(PT_SENS1-Pad8)") (class "Default")
      (node (ref "PT_SENS1") (pin "8") (pinfunction "8_8") (pintype "bidirectional"))
    )
    (net (code "37") (name "unconnected-(PT_SENS1-PadS1)") (class "Default")
      (node (ref "PT_SENS1") (pin "S1") (pinfunction "S1_S1") (pintype "bidirectional"))
    )
    (net (code "38") (name "unconnected-(PT_SENS1-PadS2)") (class "Default")
      (node (ref "PT_SENS1") (pin "S2") (pinfunction "S2_S2") (pintype "bidirectional"))
    )
    (net (code "39") (name "unconnected-(PT_SENS2-PadS1)") (class "Default")
      (node (ref "PT_SENS2") (pin "S1") (pinfunction "S1_S1") (pintype "bidirectional"))
    )
    (net (code "40") (name "unconnected-(PT_SENS2-PadS2)") (class "Default")
      (node (ref "PT_SENS2") (pin "S2") (pinfunction "S2_S2") (pintype "bidirectional"))
    )
    (net (code "41") (name "unconnected-(WB_SENS1-Pad3)") (class "Default")
      (node (ref "WB_SENS1") (pin "3") (pinfunction "3_3") (pintype "bidirectional"))
    )
    (net (code "42") (name "unconnected-(WB_SENS1-Pad4)") (class "Default")
      (node (ref "WB_SENS1") (pin "4") (pinfunction "4_4") (pintype "bidirectional"))
    )
    (net (code "43") (name "unconnected-(WB_SENS1-PadS1)") (class "Default")
      (node (ref "WB_SENS1") (pin "S1") (pinfunction "S1_S1") (pintype "bidirectional"))
    )
    (net (code "44") (name "unconnected-(WB_SENS1-PadS2)") (class "Default")
      (node (ref "WB_SENS1") (pin "S2") (pinfunction "S2_S2") (pintype "bidirectional"))
    )
    (net (code "45") (name "unconnected-(WB_SENS2-PadS1)") (class "Default")
      (node (ref "WB_SENS2") (pin "S1") (pinfunction "S1_S1") (pintype "bidirectional"))
    )
    (net (code "46") (name "unconnected-(WB_SENS2-PadS2)") (class "Default")
      (node (ref "WB_SENS2") (pin "S2") (pinfunction "S2_S2") (pintype "bidirectional"))
    )
  )
)
